# 06_ALU_IN.net
KiCad netlist of a schematic drawn in EAGLE
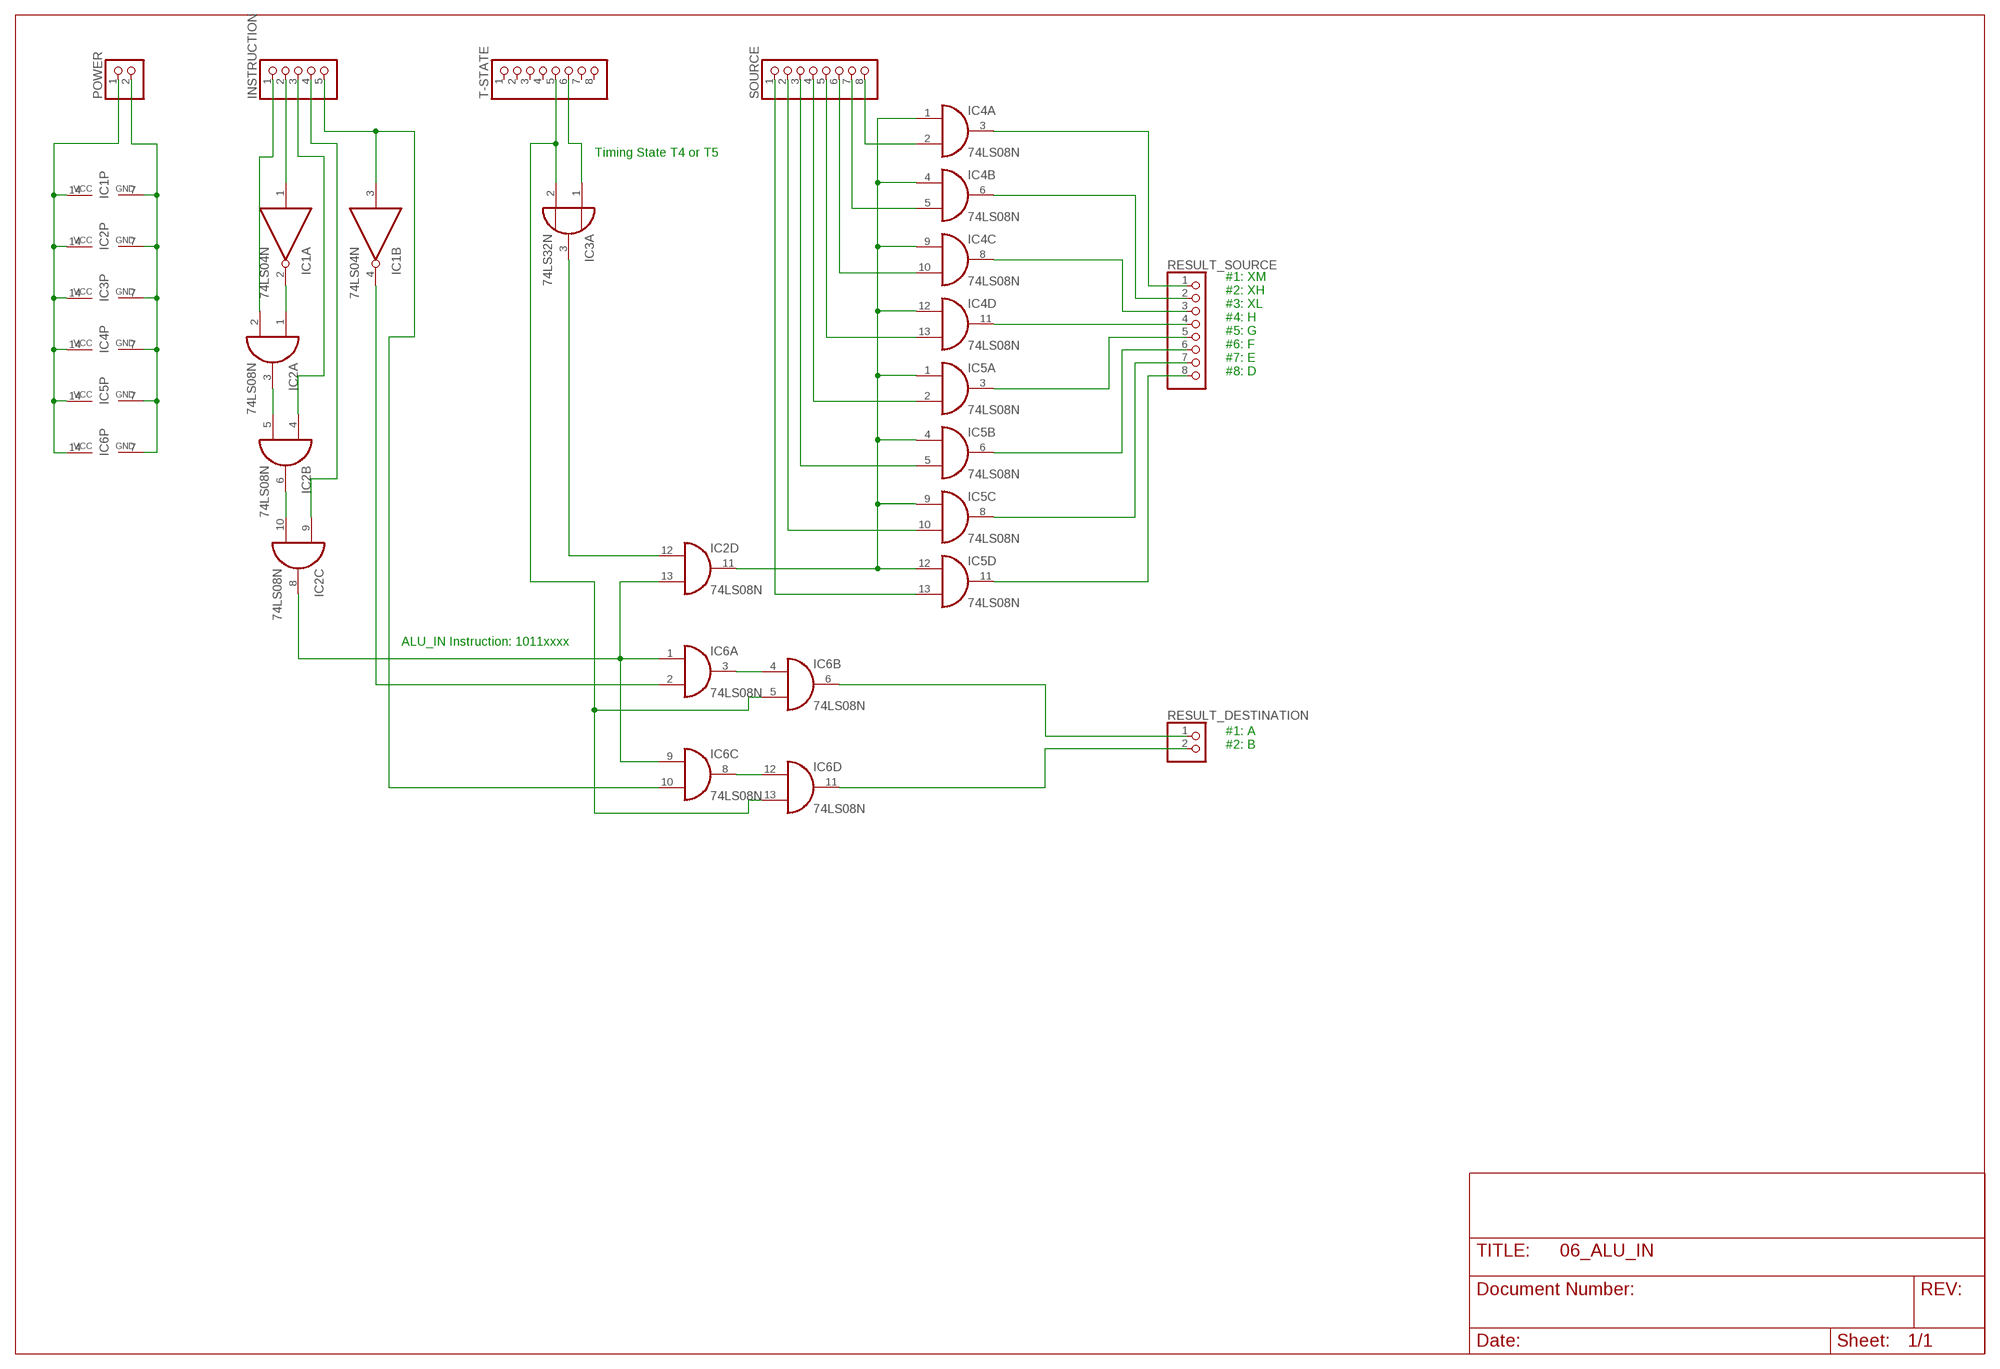
[diagram p0: schematic, sheet 1]

(export (version "E")
  (design (tool "Eeschema 10.0.6"))
  (components
    (comp (ref "IC1")
      (value "74LS04N")
      (footprint "eagle-import:DIL14")
      (libsource (lib "eagle-import") (part "7404NLS"))
    )
    (comp (ref "IC2")
      (value "74LS08N")
      (footprint "eagle-import:DIL14")
      (libsource (lib "eagle-import") (part "7408NLS"))
    )
    (comp (ref "IC3")
      (value "74LS32N")
      (footprint "eagle-import:DIL14")
      (libsource (lib "eagle-import") (part "7432NLS"))
    )
    (comp (ref "IC4")
      (value "74LS08N")
      (footprint "eagle-import:DIL14")
      (libsource (lib "eagle-import") (part "7408NLS"))
    )
    (comp (ref "IC5")
      (value "74LS08N")
      (footprint "eagle-import:DIL14")
      (libsource (lib "eagle-import") (part "7408NLS"))
    )
    (comp (ref "IC6")
      (value "74LS08N")
      (footprint "eagle-import:DIL14")
      (libsource (lib "eagle-import") (part "7408NLS"))
    )
    (comp (ref "INSTRUCTION")
      (value "PINHD-1X5")
      (footprint "eagle-import:1X05")
      (libsource (lib "eagle-import") (part "PINHD-1X5"))
    )
    (comp (ref "POWER")
      (value "PINHD-1X2")
      (footprint "eagle-import:1X02")
      (libsource (lib "eagle-import") (part "PINHD-1X2"))
    )
    (comp (ref "RESULT_DESTINATION")
      (value "PINHD-1X2")
      (footprint "eagle-import:1X02")
      (libsource (lib "eagle-import") (part "PINHD-1X2"))
    )
    (comp (ref "RESULT_SOURCE")
      (value "PINHD-1X8")
      (footprint "eagle-import:1X08")
      (libsource (lib "eagle-import") (part "PINHD-1X8"))
    )
    (comp (ref "SOURCE")
      (value "PINHD-1X8")
      (footprint "eagle-import:1X08")
      (libsource (lib "eagle-import") (part "PINHD-1X8"))
    )
    (comp (ref "T-STATE")
      (value "PINHD-1X8")
      (footprint "eagle-import:1X08")
      (libsource (lib "eagle-import") (part "PINHD-1X8"))
    )
  )
  (nets
    (net (code "1") (name "Net-(IC1A-I)") (class "Default")
      (node (ref "IC1") (pin "1") (pinfunction "I_1") (pintype "input"))
      (node (ref "INSTRUCTION") (pin "2") (pinfunction "2_2") (pintype "passive"))
    )
    (net (code "2") (name "Net-(IC1A-O)") (class "Default")
      (node (ref "IC1") (pin "2") (pinfunction "O_2") (pintype "output"))
      (node (ref "IC2") (pin "1") (pinfunction "I0_1") (pintype "input"))
    )
    (net (code "3") (name "Net-(IC1B-I)") (class "Default")
      (node (ref "IC1") (pin "3") (pinfunction "I_3") (pintype "input"))
      (node (ref "IC6") (pin "10") (pinfunction "I1_10") (pintype "input"))
      (node (ref "INSTRUCTION") (pin "5") (pinfunction "5_5") (pintype "passive"))
    )
    (net (code "4") (name "Net-(IC1B-O)") (class "Default")
      (node (ref "IC1") (pin "4") (pinfunction "O_4") (pintype "output"))
      (node (ref "IC6") (pin "2") (pinfunction "I1_2") (pintype "input"))
    )
    (net (code "5") (name "Net-(IC1G-GND)") (class "Default")
      (node (ref "IC1") (pin "7") (pinfunction "GND_7") (pintype "power_in"))
      (node (ref "IC2") (pin "7") (pinfunction "GND_7") (pintype "power_in"))
      (node (ref "IC3") (pin "7") (pinfunction "GND_7") (pintype "power_in"))
      (node (ref "IC4") (pin "7") (pinfunction "GND_7") (pintype "power_in"))
      (node (ref "IC5") (pin "7") (pinfunction "GND_7") (pintype "power_in"))
      (node (ref "IC6") (pin "7") (pinfunction "GND_7") (pintype "power_in"))
      (node (ref "POWER") (pin "2") (pinfunction "2_2") (pintype "passive"))
    )
    (net (code "6") (name "Net-(IC1G-VCC)") (class "Default")
      (node (ref "IC1") (pin "14") (pinfunction "VCC_14") (pintype "power_in"))
      (node (ref "IC2") (pin "14") (pinfunction "VCC_14") (pintype "power_in"))
      (node (ref "IC3") (pin "14") (pinfunction "VCC_14") (pintype "power_in"))
      (node (ref "IC4") (pin "14") (pinfunction "VCC_14") (pintype "power_in"))
      (node (ref "IC5") (pin "14") (pinfunction "VCC_14") (pintype "power_in"))
      (node (ref "IC6") (pin "14") (pinfunction "VCC_14") (pintype "power_in"))
      (node (ref "POWER") (pin "1") (pinfunction "1_1") (pintype "passive"))
    )
    (net (code "7") (name "Net-(IC2A-I1)") (class "Default")
      (node (ref "IC2") (pin "2") (pinfunction "I1_2") (pintype "input"))
      (node (ref "INSTRUCTION") (pin "1") (pinfunction "1_1") (pintype "passive"))
    )
    (net (code "8") (name "Net-(IC2A-O)") (class "Default")
      (node (ref "IC2") (pin "3") (pinfunction "O_3") (pintype "output"))
      (node (ref "IC2") (pin "5") (pinfunction "I1_5") (pintype "input"))
    )
    (net (code "9") (name "Net-(IC2B-I0)") (class "Default")
      (node (ref "IC2") (pin "4") (pinfunction "I0_4") (pintype "input"))
      (node (ref "INSTRUCTION") (pin "3") (pinfunction "3_3") (pintype "passive"))
    )
    (net (code "10") (name "Net-(IC2B-O)") (class "Default")
      (node (ref "IC2") (pin "10") (pinfunction "I1_10") (pintype "input"))
      (node (ref "IC2") (pin "6") (pinfunction "O_6") (pintype "output"))
    )
    (net (code "11") (name "Net-(IC2C-I0)") (class "Default")
      (node (ref "IC2") (pin "9") (pinfunction "I0_9") (pintype "input"))
      (node (ref "INSTRUCTION") (pin "4") (pinfunction "4_4") (pintype "passive"))
    )
    (net (code "12") (name "Net-(IC2C-O)") (class "Default")
      (node (ref "IC2") (pin "13") (pinfunction "I1_13") (pintype "input"))
      (node (ref "IC2") (pin "8") (pinfunction "O_8") (pintype "output"))
      (node (ref "IC6") (pin "1") (pinfunction "I0_1") (pintype "input"))
      (node (ref "IC6") (pin "9") (pinfunction "I0_9") (pintype "input"))
    )
    (net (code "13") (name "Net-(IC2D-I0)") (class "Default")
      (node (ref "IC2") (pin "12") (pinfunction "I0_12") (pintype "input"))
      (node (ref "IC3") (pin "3") (pinfunction "O_3") (pintype "output"))
    )
    (net (code "14") (name "Net-(IC2D-O)") (class "Default")
      (node (ref "IC2") (pin "11") (pinfunction "O_11") (pintype "output"))
      (node (ref "IC4") (pin "1") (pinfunction "I0_1") (pintype "input"))
      (node (ref "IC4") (pin "12") (pinfunction "I0_12") (pintype "input"))
      (node (ref "IC4") (pin "4") (pinfunction "I0_4") (pintype "input"))
      (node (ref "IC4") (pin "9") (pinfunction "I0_9") (pintype "input"))
      (node (ref "IC5") (pin "1") (pinfunction "I0_1") (pintype "input"))
      (node (ref "IC5") (pin "12") (pinfunction "I0_12") (pintype "input"))
      (node (ref "IC5") (pin "4") (pinfunction "I0_4") (pintype "input"))
      (node (ref "IC5") (pin "9") (pinfunction "I0_9") (pintype "input"))
    )
    (net (code "15") (name "Net-(IC3A-I0)") (class "Default")
      (node (ref "IC3") (pin "1") (pinfunction "I0_1") (pintype "input"))
      (node (ref "T-STATE") (pin "6") (pinfunction "6_6") (pintype "passive"))
    )
    (net (code "16") (name "Net-(IC3A-I1)") (class "Default")
      (node (ref "IC3") (pin "2") (pinfunction "I1_2") (pintype "input"))
      (node (ref "IC6") (pin "13") (pinfunction "I1_13") (pintype "input"))
      (node (ref "IC6") (pin "5") (pinfunction "I1_5") (pintype "input"))
      (node (ref "T-STATE") (pin "5") (pinfunction "5_5") (pintype "passive"))
    )
    (net (code "17") (name "Net-(IC4A-I1)") (class "Default")
      (node (ref "IC4") (pin "2") (pinfunction "I1_2") (pintype "input"))
      (node (ref "SOURCE") (pin "8") (pinfunction "8_8") (pintype "passive"))
    )
    (net (code "18") (name "Net-(IC4A-O)") (class "Default")
      (node (ref "IC4") (pin "3") (pinfunction "O_3") (pintype "output"))
      (node (ref "RESULT_SOURCE") (pin "1") (pinfunction "1_1") (pintype "passive"))
    )
    (net (code "19") (name "Net-(IC4B-I1)") (class "Default")
      (node (ref "IC4") (pin "5") (pinfunction "I1_5") (pintype "input"))
      (node (ref "SOURCE") (pin "7") (pinfunction "7_7") (pintype "passive"))
    )
    (net (code "20") (name "Net-(IC4B-O)") (class "Default")
      (node (ref "IC4") (pin "6") (pinfunction "O_6") (pintype "output"))
      (node (ref "RESULT_SOURCE") (pin "2") (pinfunction "2_2") (pintype "passive"))
    )
    (net (code "21") (name "Net-(IC4C-I1)") (class "Default")
      (node (ref "IC4") (pin "10") (pinfunction "I1_10") (pintype "input"))
      (node (ref "SOURCE") (pin "6") (pinfunction "6_6") (pintype "passive"))
    )
    (net (code "22") (name "Net-(IC4C-O)") (class "Default")
      (node (ref "IC4") (pin "8") (pinfunction "O_8") (pintype "output"))
      (node (ref "RESULT_SOURCE") (pin "3") (pinfunction "3_3") (pintype "passive"))
    )
    (net (code "23") (name "Net-(IC4D-I1)") (class "Default")
      (node (ref "IC4") (pin "13") (pinfunction "I1_13") (pintype "input"))
      (node (ref "SOURCE") (pin "5") (pinfunction "5_5") (pintype "passive"))
    )
    (net (code "24") (name "Net-(IC4D-O)") (class "Default")
      (node (ref "IC4") (pin "11") (pinfunction "O_11") (pintype "output"))
      (node (ref "RESULT_SOURCE") (pin "4") (pinfunction "4_4") (pintype "passive"))
    )
    (net (code "25") (name "Net-(IC5A-I1)") (class "Default")
      (node (ref "IC5") (pin "2") (pinfunction "I1_2") (pintype "input"))
      (node (ref "SOURCE") (pin "4") (pinfunction "4_4") (pintype "passive"))
    )
    (net (code "26") (name "Net-(IC5A-O)") (class "Default")
      (node (ref "IC5") (pin "3") (pinfunction "O_3") (pintype "output"))
      (node (ref "RESULT_SOURCE") (pin "5") (pinfunction "5_5") (pintype "passive"))
    )
    (net (code "27") (name "Net-(IC5B-I1)") (class "Default")
      (node (ref "IC5") (pin "5") (pinfunction "I1_5") (pintype "input"))
      (node (ref "SOURCE") (pin "3") (pinfunction "3_3") (pintype "passive"))
    )
    (net (code "28") (name "Net-(IC5B-O)") (class "Default")
      (node (ref "IC5") (pin "6") (pinfunction "O_6") (pintype "output"))
      (node (ref "RESULT_SOURCE") (pin "6") (pinfunction "6_6") (pintype "passive"))
    )
    (net (code "29") (name "Net-(IC5C-I1)") (class "Default")
      (node (ref "IC5") (pin "10") (pinfunction "I1_10") (pintype "input"))
      (node (ref "SOURCE") (pin "2") (pinfunction "2_2") (pintype "passive"))
    )
    (net (code "30") (name "Net-(IC5C-O)") (class "Default")
      (node (ref "IC5") (pin "8") (pinfunction "O_8") (pintype "output"))
      (node (ref "RESULT_SOURCE") (pin "7") (pinfunction "7_7") (pintype "passive"))
    )
    (net (code "31") (name "Net-(IC5D-I1)") (class "Default")
      (node (ref "IC5") (pin "13") (pinfunction "I1_13") (pintype "input"))
      (node (ref "SOURCE") (pin "1") (pinfunction "1_1") (pintype "passive"))
    )
    (net (code "32") (name "Net-(IC5D-O)") (class "Default")
      (node (ref "IC5") (pin "11") (pinfunction "O_11") (pintype "output"))
      (node (ref "RESULT_SOURCE") (pin "8") (pinfunction "8_8") (pintype "passive"))
    )
    (net (code "33") (name "Net-(IC6A-O)") (class "Default")
      (node (ref "IC6") (pin "3") (pinfunction "O_3") (pintype "output"))
      (node (ref "IC6") (pin "4") (pinfunction "I0_4") (pintype "input"))
    )
    (net (code "34") (name "Net-(IC6B-O)") (class "Default")
      (node (ref "IC6") (pin "6") (pinfunction "O_6") (pintype "output"))
      (node (ref "RESULT_DESTINATION") (pin "1") (pinfunction "1_1") (pintype "passive"))
    )
    (net (code "35") (name "Net-(IC6C-O)") (class "Default")
      (node (ref "IC6") (pin "12") (pinfunction "I0_12") (pintype "input"))
      (node (ref "IC6") (pin "8") (pinfunction "O_8") (pintype "output"))
    )
    (net (code "36") (name "Net-(IC6D-O)") (class "Default")
      (node (ref "IC6") (pin "11") (pinfunction "O_11") (pintype "output"))
      (node (ref "RESULT_DESTINATION") (pin "2") (pinfunction "2_2") (pintype "passive"))
    )
    (net (code "37") (name "unconnected-(T-STATE-Pad1)") (class "Default")
      (node (ref "T-STATE") (pin "1") (pinfunction "1_1") (pintype "passive"))
    )
    (net (code "38") (name "unconnected-(T-STATE-Pad2)") (class "Default")
      (node (ref "T-STATE") (pin "2") (pinfunction "2_2") (pintype "passive"))
    )
    (net (code "39") (name "unconnected-(T-STATE-Pad3)") (class "Default")
      (node (ref "T-STATE") (pin "3") (pinfunction "3_3") (pintype "passive"))
    )
    (net (code "40") (name "unconnected-(T-STATE-Pad4)") (class "Default")
      (node (ref "T-STATE") (pin "4") (pinfunction "4_4") (pintype "passive"))
    )
    (net (code "41") (name "unconnected-(T-STATE-Pad7)") (class "Default")
      (node (ref "T-STATE") (pin "7") (pinfunction "7_7") (pintype "passive"))
    )
    (net (code "42") (name "unconnected-(T-STATE-Pad8)") (class "Default")
      (node (ref "T-STATE") (pin "8") (pinfunction "8_8") (pintype "passive"))
    )
  )
)
